# USB-C.net
KiCad netlist of a schematic drawn in Altium Designer
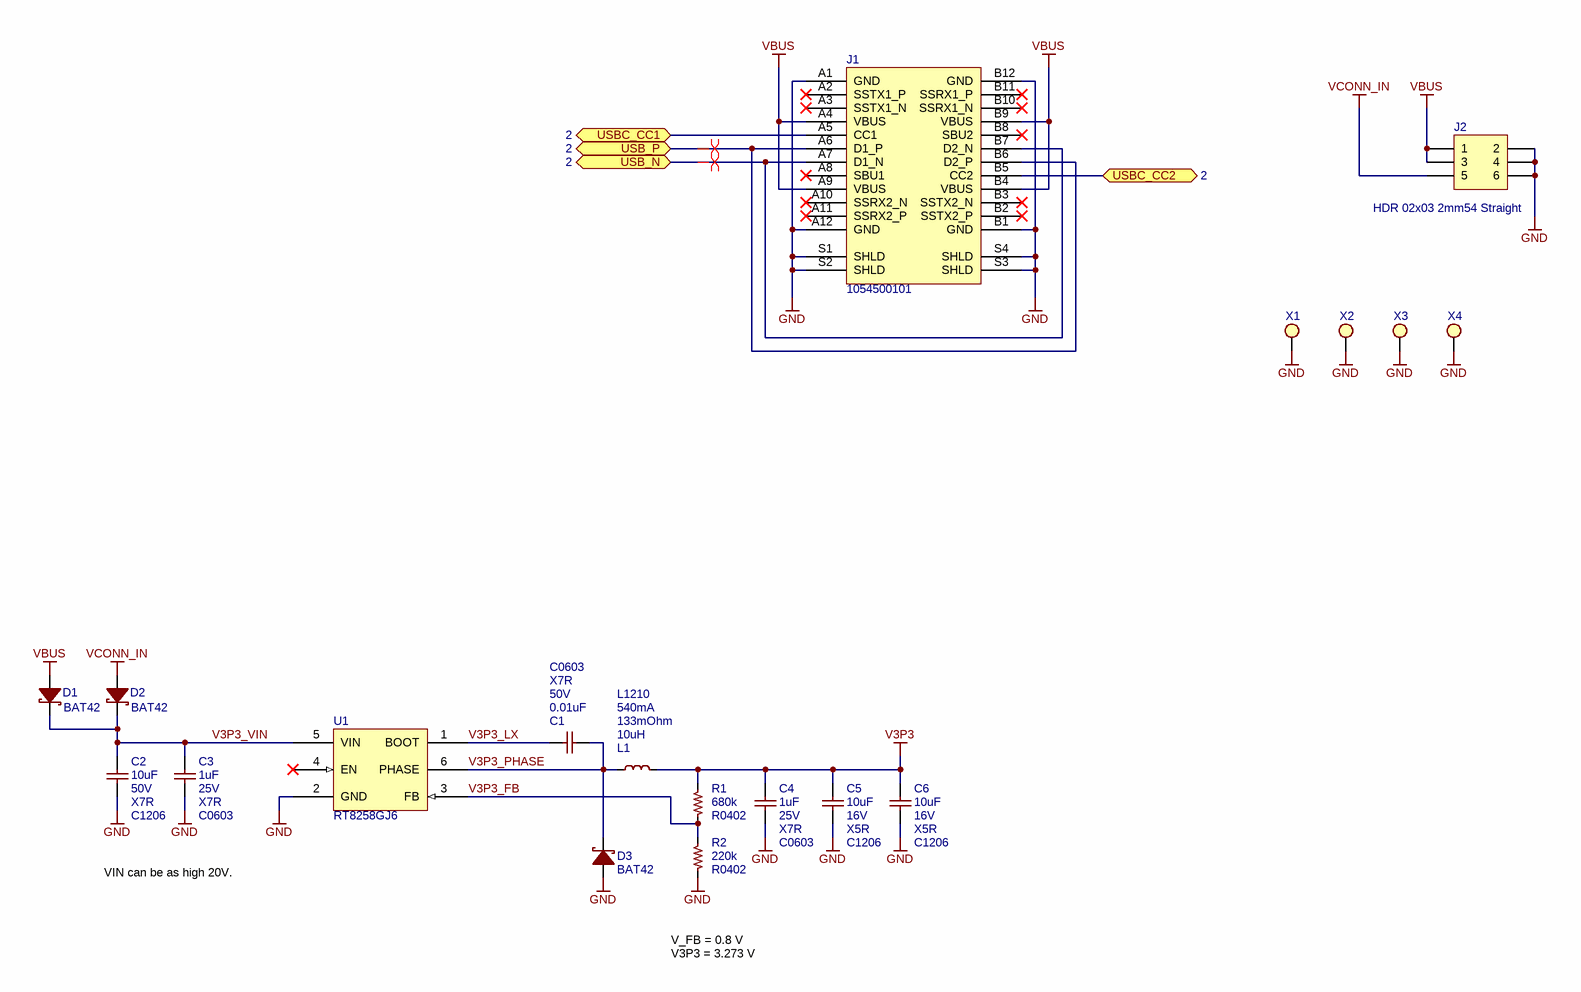
[diagram p0: USB-C.SchDoc]

(export (version "E")
  (design (tool "Eeschema 10.0.6"))
  (components
    (comp (ref "C1")
      (value "0.01uF")
      (footprint "C0603")
      (fields
        (field (name "VOLTAGE") "50V")
        (field (name "MATERIAL") "X7R")
        (field (name "Comment") "MF-CAP-0603-0.01uF")
      )
      (libsource (lib "ReclaimerLabs") (part "CAPACITOR_NP"))
    )
    (comp (ref "C2")
      (value "10uF")
      (footprint "C1206")
      (fields
        (field (name "VOLTAGE") "50V")
        (field (name "MATERIAL") "X7R")
        (field (name "Comment") "CL31B106KBHNNNE")
      )
      (libsource (lib "ReclaimerLabs") (part "CAPACITOR_NP"))
    )
    (comp (ref "C3")
      (value "1uF")
      (footprint "C0603")
      (fields
        (field (name "VOLTAGE") "25V")
        (field (name "MATERIAL") "X7R")
        (field (name "Comment") "MF-CAP-0603-1uF")
      )
      (libsource (lib "ReclaimerLabs") (part "CAPACITOR_NP"))
    )
    (comp (ref "C4")
      (value "1uF")
      (footprint "C0603")
      (fields
        (field (name "VOLTAGE") "25V")
        (field (name "MATERIAL") "X7R")
        (field (name "Comment") "MF-CAP-0603-1uF")
      )
      (libsource (lib "ReclaimerLabs") (part "CAPACITOR_NP"))
    )
    (comp (ref "C5")
      (value "10uF")
      (footprint "C1206")
      (fields
        (field (name "VOLTAGE") "16V")
        (field (name "MATERIAL") "X5R")
        (field (name "Comment") "MF-CAP-1206-10uF")
      )
      (libsource (lib "ReclaimerLabs") (part "CAPACITOR_NP"))
    )
    (comp (ref "C6")
      (value "10uF")
      (footprint "C1206")
      (fields
        (field (name "VOLTAGE") "16V")
        (field (name "MATERIAL") "X5R")
        (field (name "Comment") "MF-CAP-1206-10uF")
      )
      (libsource (lib "ReclaimerLabs") (part "CAPACITOR_NP"))
    )
    (comp (ref "D1")
      (value "BAT42")
      (footprint "SOD-123")
      (fields (field (name "MANUFACTURER") "MacroFab") (field (name "Comment") "MF-DIO-SOD123-BAT42"))
      (libsource (lib "ReclaimerLabs") (part "DIODE_SCHOTTKY"))
    )
    (comp (ref "D2")
      (value "BAT42")
      (footprint "SOD-123")
      (fields (field (name "MANUFACTURER") "MacroFab") (field (name "Comment") "MF-DIO-SOD123-BAT42"))
      (libsource (lib "ReclaimerLabs") (part "DIODE_SCHOTTKY"))
    )
    (comp (ref "D3")
      (value "BAT42")
      (footprint "SOD-123")
      (fields (field (name "Comment") "MF-DIO-SOD123-BAT42"))
      (libsource (lib "ReclaimerLabs") (part "DIODE_SCHOTTKY"))
    )
    (comp (ref "J1")
      (value "1054500101")
      (footprint "1054500101")
      (fields (field (name "MANUFACTURER") "Molex"))
      (libsource (lib "ReclaimerLabs") (part "USB-C_RECPT"))
    )
    (comp (ref "J2")
      (value "HDR 02x03 2mm54 Straight")
      (footprint "CONN_HEADER_02x03_2mm54_Straight")
      (fields (field (name "Comment") "MF-CON-2.54mm-2x3"))
      (libsource (lib "ReclaimerLabs") (part "CONN_HEADER_02x03_2mm54_Straight"))
    )
    (comp (ref "L1")
      (value "10uH")
      (footprint "L1210")
      (fields
        (field (name "DCR") "133mOhm")
        (field (name "CURRENT") "540mA")
        (field (name "Comment") "MF-IND-1210-10uH")
      )
      (libsource (lib "ReclaimerLabs") (part "INDUCTOR"))
    )
    (comp (ref "R1")
      (value "680k")
      (footprint "ReclaimerLabs:R0402")
      (fields (field (name "Comment") "MF-RES-0402-680K"))
      (libsource (lib "ReclaimerLabs") (part "RESISTOR"))
    )
    (comp (ref "R2")
      (value "220k")
      (footprint "ReclaimerLabs:R0402")
      (fields (field (name "Comment") "MF-RES-0402-220K"))
      (libsource (lib "ReclaimerLabs") (part "RESISTOR"))
    )
    (comp (ref "U1")
      (value "RT8258GJ6")
      (footprint "SOT23-6")
      (libsource (lib "ReclaimerLabs") (part "BUCK_RT8258GJ6"))
    )
    (comp (ref "X1") (value "MTHOLE") (libsource (lib "ReclaimerLabs") (part "MTHOLE")))
    (comp (ref "X2") (value "MTHOLE") (libsource (lib "ReclaimerLabs") (part "MTHOLE")))
    (comp (ref "X3") (value "MTHOLE") (libsource (lib "ReclaimerLabs") (part "MTHOLE")))
    (comp (ref "X4") (value "MTHOLE") (libsource (lib "ReclaimerLabs") (part "MTHOLE")))
  )
  (nets
    (net (code "1") (name "/USBC_CC1") (class "Default")
      (node (ref "J1") (pin "A5") (pinfunction "CC1_A5") (pintype "passive"))
    )
    (net (code "2") (name "/USBC_CC2") (class "Default")
      (node (ref "J1") (pin "B5") (pinfunction "CC2_B5") (pintype "passive"))
    )
    (net (code "3") (name "/USB_N") (class "Default")
      (node (ref "J1") (pin "A7") (pinfunction "D1_N_A7") (pintype "passive"))
      (node (ref "J1") (pin "B7") (pinfunction "D2_N_B7") (pintype "passive"))
    )
    (net (code "4") (name "/USB_P") (class "Default")
      (node (ref "J1") (pin "A6") (pinfunction "D1_P_A6") (pintype "passive"))
      (node (ref "J1") (pin "B6") (pinfunction "D2_P_B6") (pintype "passive"))
    )
    (net (code "5") (name "/V3P3_FB") (class "Default")
      (node (ref "R1") (pin "2") (pinfunction "R2_2") (pintype "passive"))
      (node (ref "R2") (pin "1") (pinfunction "R1_1") (pintype "passive"))
      (node (ref "U1") (pin "3") (pinfunction "FB_3") (pintype "input"))
    )
    (net (code "6") (name "/V3P3_LX") (class "Default")
      (node (ref "C1") (pin "1") (pinfunction "C1_1") (pintype "passive"))
      (node (ref "U1") (pin "1") (pinfunction "BOOT_1") (pintype "power_in"))
    )
    (net (code "7") (name "/V3P3_PHASE") (class "Default")
      (node (ref "C1") (pin "2") (pinfunction "C2_2") (pintype "passive"))
      (node (ref "D3") (pin "1") (pinfunction "C1_1") (pintype "passive"))
      (node (ref "L1") (pin "1") (pinfunction "R1_1") (pintype "passive"))
      (node (ref "U1") (pin "6") (pinfunction "PHASE_6") (pintype "power_in"))
    )
    (net (code "8") (name "/V3P3_VIN") (class "Default")
      (node (ref "C2") (pin "1") (pinfunction "C1_1") (pintype "passive"))
      (node (ref "C3") (pin "1") (pinfunction "C1_1") (pintype "passive"))
      (node (ref "D1") (pin "1") (pinfunction "C1_1") (pintype "passive"))
      (node (ref "D2") (pin "1") (pinfunction "C1_1") (pintype "passive"))
      (node (ref "U1") (pin "5") (pinfunction "VIN_5") (pintype "power_in"))
    )
    (net (code "9") (name "GND") (class "Default")
      (node (ref "C2") (pin "2") (pinfunction "C2_2") (pintype "passive"))
      (node (ref "C3") (pin "2") (pinfunction "C2_2") (pintype "passive"))
      (node (ref "C4") (pin "2") (pinfunction "C2_2") (pintype "passive"))
      (node (ref "C5") (pin "2") (pinfunction "C2_2") (pintype "passive"))
      (node (ref "C6") (pin "2") (pinfunction "C2_2") (pintype "passive"))
      (node (ref "D3") (pin "2") (pinfunction "C2_2") (pintype "passive"))
      (node (ref "J1") (pin "A1") (pinfunction "GND_A1") (pintype "passive"))
      (node (ref "J1") (pin "A12") (pinfunction "GND_A12") (pintype "passive"))
      (node (ref "J1") (pin "B1") (pinfunction "GND_B1") (pintype "passive"))
      (node (ref "J1") (pin "B12") (pinfunction "GND_B12") (pintype "passive"))
      (node (ref "J1") (pin "S1") (pinfunction "SHLD_S1") (pintype "passive"))
      (node (ref "J1") (pin "S2") (pinfunction "SHLD_S2") (pintype "passive"))
      (node (ref "J1") (pin "S3") (pinfunction "SHLD_S3") (pintype "passive"))
      (node (ref "J1") (pin "S4") (pinfunction "SHLD_S4") (pintype "passive"))
      (node (ref "J2") (pin "2") (pinfunction "2_2") (pintype "power_in"))
      (node (ref "J2") (pin "4") (pinfunction "4_4") (pintype "power_in"))
      (node (ref "J2") (pin "6") (pinfunction "6_6") (pintype "power_in"))
      (node (ref "R2") (pin "2") (pinfunction "R2_2") (pintype "passive"))
      (node (ref "U1") (pin "2") (pinfunction "GND_2") (pintype "passive"))
      (node (ref "X1") (pin "1") (pinfunction "1_1") (pintype "passive"))
      (node (ref "X2") (pin "1") (pinfunction "1_1") (pintype "passive"))
      (node (ref "X3") (pin "1") (pinfunction "1_1") (pintype "passive"))
      (node (ref "X4") (pin "1") (pinfunction "1_1") (pintype "passive"))
    )
    (net (code "10") (name "V3P3") (class "Default")
      (node (ref "C4") (pin "1") (pinfunction "C1_1") (pintype "passive"))
      (node (ref "C5") (pin "1") (pinfunction "C1_1") (pintype "passive"))
      (node (ref "C6") (pin "1") (pinfunction "C1_1") (pintype "passive"))
      (node (ref "L1") (pin "2") (pinfunction "R2_2") (pintype "passive"))
      (node (ref "R1") (pin "1") (pinfunction "R1_1") (pintype "passive"))
    )
    (net (code "11") (name "VBUS") (class "Default")
      (node (ref "D1") (pin "2") (pinfunction "C2_2") (pintype "passive"))
      (node (ref "J1") (pin "A4") (pinfunction "VBUS_A4") (pintype "passive"))
      (node (ref "J1") (pin "A9") (pinfunction "VBUS_A9") (pintype "passive"))
      (node (ref "J1") (pin "B4") (pinfunction "VBUS_B4") (pintype "passive"))
      (node (ref "J1") (pin "B9") (pinfunction "VBUS_B9") (pintype "passive"))
      (node (ref "J2") (pin "1") (pinfunction "1_1") (pintype "power_in"))
      (node (ref "J2") (pin "3") (pinfunction "3_3") (pintype "power_in"))
    )
    (net (code "12") (name "VCONN_IN") (class "Default")
      (node (ref "D2") (pin "2") (pinfunction "C2_2") (pintype "passive"))
      (node (ref "J2") (pin "5") (pinfunction "5_5") (pintype "power_in"))
    )
    (net (code "13") (name "unconnected-(J1-SBU1-PadA8)") (class "Default")
      (node (ref "J1") (pin "A8") (pinfunction "SBU1_A8") (pintype "passive+no_connect"))
    )
    (net (code "14") (name "unconnected-(J1-SBU2-PadB8)") (class "Default")
      (node (ref "J1") (pin "B8") (pinfunction "SBU2_B8") (pintype "passive+no_connect"))
    )
    (net (code "15") (name "unconnected-(J1-SSRX1_N-PadB10)") (class "Default")
      (node (ref "J1") (pin "B10") (pinfunction "SSRX1_N_B10") (pintype "passive+no_connect"))
    )
    (net (code "16") (name "unconnected-(J1-SSRX1_P-PadB11)") (class "Default")
      (node (ref "J1") (pin "B11") (pinfunction "SSRX1_P_B11") (pintype "passive+no_connect"))
    )
    (net (code "17") (name "unconnected-(J1-SSRX2_N-PadA10)") (class "Default")
      (node (ref "J1") (pin "A10") (pinfunction "SSRX2_N_A10") (pintype "passive+no_connect"))
    )
    (net (code "18") (name "unconnected-(J1-SSRX2_P-PadA11)") (class "Default")
      (node (ref "J1") (pin "A11") (pinfunction "SSRX2_P_A11") (pintype "passive+no_connect"))
    )
    (net (code "19") (name "unconnected-(J1-SSTX1_N-PadA3)") (class "Default")
      (node (ref "J1") (pin "A3") (pinfunction "SSTX1_N_A3") (pintype "passive+no_connect"))
    )
    (net (code "20") (name "unconnected-(J1-SSTX1_P-PadA2)") (class "Default")
      (node (ref "J1") (pin "A2") (pinfunction "SSTX1_P_A2") (pintype "passive+no_connect"))
    )
    (net (code "21") (name "unconnected-(J1-SSTX2_N-PadB3)") (class "Default")
      (node (ref "J1") (pin "B3") (pinfunction "SSTX2_N_B3") (pintype "passive+no_connect"))
    )
    (net (code "22") (name "unconnected-(J1-SSTX2_P-PadB2)") (class "Default")
      (node (ref "J1") (pin "B2") (pinfunction "SSTX2_P_B2") (pintype "passive+no_connect"))
    )
    (net (code "23") (name "unconnected-(U1-EN-Pad4)") (class "Default")
      (node (ref "U1") (pin "4") (pinfunction "EN_4") (pintype "input+no_connect"))
    )
  )
)
